# AblationChannel.net
KiCad netlist of a schematic drawn in Altium Designer
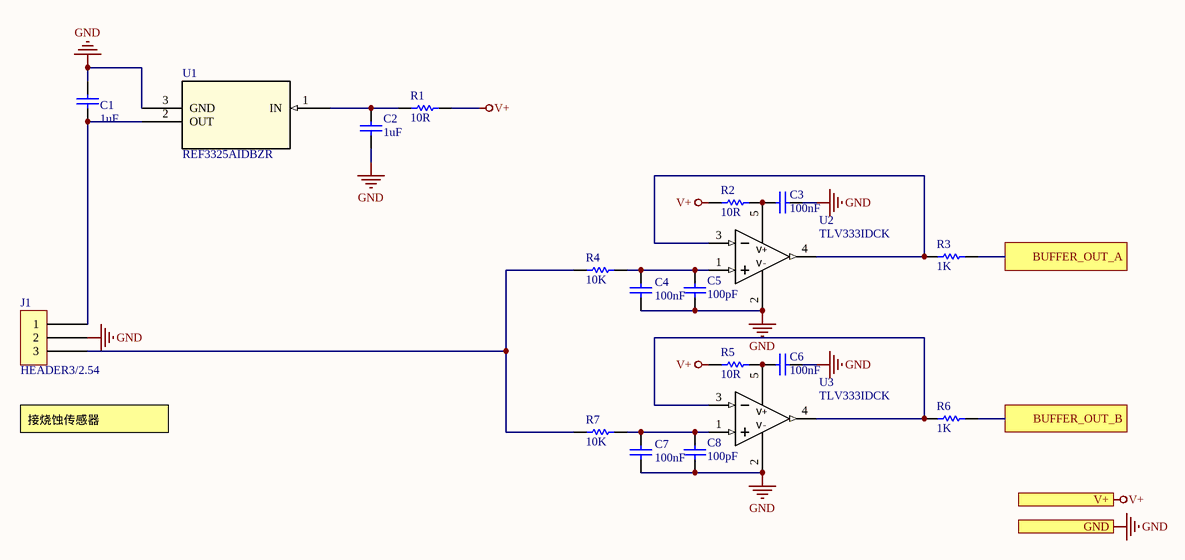
[diagram p0: AblationChannel.SchDoc]

(export (version "E")
  (design (tool "Eeschema 10.0.6"))
  (components
    (comp (ref "C1")
      (value "1uF")
      (footprint "R0603_C")
      (description "精度 ±10% \r\n容值 1uF \r\n额定电压 50V \r\n温漂系数（介质材料) X7R")
      (libsource (lib "00Lib") (part "1uF/0603/50V"))
    )
    (comp (ref "C2")
      (value "1uF")
      (footprint "R0603_C")
      (description "精度 ±10% \r\n容值 1uF \r\n额定电压 50V \r\n温漂系数（介质材料) X7R")
      (libsource (lib "00Lib") (part "1uF/0603/50V"))
    )
    (comp (ref "C3")
      (value "100nF")
      (footprint "R0603_C")
      (description "精度 ±10% \r\n容值 100nF \r\n额定电压 50V \r\n温漂系数（介质材料) X7R")
      (libsource (lib "00Lib") (part "100nF/0603/50V"))
    )
    (comp (ref "C4")
      (value "100nF")
      (footprint "R0603_C")
      (description "精度 ±10% \r\n容值 100nF \r\n额定电压 50V \r\n温漂系数（介质材料) X7R")
      (libsource (lib "00Lib") (part "100nF/0603/50V"))
    )
    (comp (ref "C5")
      (value "100pF")
      (footprint "R0603_C")
      (description "精度 ±5% \r\n容值 100pF \r\n额定电压 50V \r\n温漂系数（介质材料) C0G")
      (libsource (lib "00Lib") (part "100pF/0603/50V"))
    )
    (comp (ref "C6")
      (value "100nF")
      (footprint "R0603_C")
      (description "精度 ±10% \r\n容值 100nF \r\n额定电压 50V \r\n温漂系数（介质材料) X7R")
      (libsource (lib "00Lib") (part "100nF/0603/50V"))
    )
    (comp (ref "C7")
      (value "100nF")
      (footprint "R0603_C")
      (description "精度 ±10% \r\n容值 100nF \r\n额定电压 50V \r\n温漂系数（介质材料) X7R")
      (libsource (lib "00Lib") (part "100nF/0603/50V"))
    )
    (comp (ref "C8")
      (value "100pF")
      (footprint "R0603_C")
      (description "精度 ±5% \r\n容值 100pF \r\n额定电压 50V \r\n温漂系数（介质材料) C0G")
      (libsource (lib "00Lib") (part "100pF/0603/50V"))
    )
    (comp (ref "J1")
      (value "HEADER3/2.54")
      (footprint "SIP3/2.54")
      (description "3pin,单排,2.54mm间距")
      (libsource (lib "00Lib") (part "HEADER3/2.54"))
    )
    (comp (ref "R1")
      (value "10R")
      (footprint "R0603_R")
      (description "精度 ±1% \r\n阻值 10Ω \r\n温度系数 ±100ppm/℃ \r\n功率 0.1W")
      (libsource (lib "00Lib") (part "10R/0603"))
    )
    (comp (ref "R2")
      (value "10R")
      (footprint "R0603_R")
      (description "精度 ±1% \r\n阻值 10Ω \r\n温度系数 ±100ppm/℃ \r\n功率 0.1W")
      (libsource (lib "00Lib") (part "10R/0603"))
    )
    (comp (ref "R3")
      (value "1K")
      (footprint "R0603_R")
      (description "精度 ±1% \r\n温度系数 ±100ppm/℃ \r\n阻值 1kΩ \r\n功率 0.1W")
      (libsource (lib "00Lib") (part "1K/0603"))
    )
    (comp (ref "R4")
      (value "10K")
      (footprint "R0603_R")
      (description "精度 ±1% \r\n温度系数 ±100ppm/℃ \r\n阻值 10kΩ \r\n功率 0.1W")
      (libsource (lib "00Lib") (part "10K/0603"))
    )
    (comp (ref "R5")
      (value "10R")
      (footprint "R0603_R")
      (description "精度 ±1% \r\n阻值 10Ω \r\n温度系数 ±100ppm/℃ \r\n功率 0.1W")
      (libsource (lib "00Lib") (part "10R/0603"))
    )
    (comp (ref "R6")
      (value "1K")
      (footprint "R0603_R")
      (description "精度 ±1% \r\n温度系数 ±100ppm/℃ \r\n阻值 1kΩ \r\n功率 0.1W")
      (libsource (lib "00Lib") (part "1K/0603"))
    )
    (comp (ref "R7")
      (value "10K")
      (footprint "R0603_R")
      (description "精度 ±1% \r\n温度系数 ±100ppm/℃ \r\n阻值 10kΩ \r\n功率 0.1W")
      (libsource (lib "00Lib") (part "10K/0603"))
    )
    (comp (ref "U1")
      (value "REF3325AIDBZR")
      (footprint "SOT-23(SOT-23-3)")
      (libsource (lib "00Lib") (part "REF3325AIDBZR"))
    )
    (comp (ref "U2")
      (value "TLV333IDCK")
      (footprint "DCK0005A_N")
      (description "电源电压 1.8V ~ 5.5V, ±0.9V ~ 2.75V\r\n增益带宽积（GBP） 350kHz \r\n压摆率（SR） 0.16 V/us \r\n工作温度 -40°C ~ 125°C")
      (libsource (lib "00Lib") (part "TLV333IDCK"))
    )
    (comp (ref "U3")
      (value "TLV333IDCK")
      (footprint "DCK0005A_N")
      (description "电源电压 1.8V ~ 5.5V, ±0.9V ~ 2.75V\r\n增益带宽积（GBP） 350kHz \r\n压摆率（SR） 0.16 V/us \r\n工作温度 -40°C ~ 125°C")
      (libsource (lib "00Lib") (part "TLV333IDCK"))
    )
  )
  (nets
    (net (code "1") (name "/BUFFER_OUT_A") (class "Default")
      (node (ref "R3") (pin "2") (pinfunction "2_2") (pintype "passive"))
    )
    (net (code "2") (name "/BUFFER_OUT_B") (class "Default")
      (node (ref "R6") (pin "2") (pinfunction "2_2") (pintype "passive"))
    )
    (net (code "3") (name "GND") (class "Default")
      (node (ref "C1") (pin "1") (pinfunction "1_1") (pintype "passive"))
      (node (ref "C2") (pin "1") (pinfunction "1_1") (pintype "passive"))
      (node (ref "C3") (pin "1") (pinfunction "1_1") (pintype "passive"))
      (node (ref "C4") (pin "2") (pinfunction "2_2") (pintype "passive"))
      (node (ref "C5") (pin "1") (pinfunction "1_1") (pintype "passive"))
      (node (ref "C6") (pin "1") (pinfunction "1_1") (pintype "passive"))
      (node (ref "C7") (pin "2") (pinfunction "2_2") (pintype "passive"))
      (node (ref "C8") (pin "1") (pinfunction "1_1") (pintype "passive"))
      (node (ref "J1") (pin "2") (pinfunction "2_2") (pintype "passive"))
      (node (ref "U1") (pin "3") (pinfunction "GND_3") (pintype "power_in"))
      (node (ref "U2") (pin "2") (pinfunction "V-_2") (pintype "power_in"))
      (node (ref "U3") (pin "2") (pinfunction "V-_2") (pintype "power_in"))
    )
    (net (code "4") (name "Net-(J1-Pad3)") (class "Default")
      (node (ref "J1") (pin "3") (pinfunction "3_3") (pintype "passive"))
      (node (ref "R4") (pin "1") (pinfunction "1_1") (pintype "passive"))
      (node (ref "R7") (pin "1") (pinfunction "1_1") (pintype "passive"))
    )
    (net (code "5") (name "Net-(U1-IN)") (class "Default")
      (node (ref "C2") (pin "2") (pinfunction "2_2") (pintype "passive"))
      (node (ref "R1") (pin "2") (pinfunction "2_2") (pintype "passive"))
      (node (ref "U1") (pin "1") (pinfunction "IN_1") (pintype "input"))
    )
    (net (code "6") (name "Net-(U1-OUT)") (class "Default")
      (node (ref "C1") (pin "2") (pinfunction "2_2") (pintype "passive"))
      (node (ref "J1") (pin "1") (pinfunction "1_1") (pintype "passive"))
      (node (ref "U1") (pin "2") (pinfunction "OUT_2") (pintype "power_in"))
    )
    (net (code "7") (name "Net-(U2-IN+)") (class "Default")
      (node (ref "C4") (pin "1") (pinfunction "1_1") (pintype "passive"))
      (node (ref "C5") (pin "2") (pinfunction "2_2") (pintype "passive"))
      (node (ref "R4") (pin "2") (pinfunction "2_2") (pintype "passive"))
      (node (ref "U2") (pin "1") (pinfunction "IN+_1") (pintype "input"))
    )
    (net (code "8") (name "Net-(U2-IN-)") (class "Default")
      (node (ref "R3") (pin "1") (pinfunction "1_1") (pintype "passive"))
      (node (ref "U2") (pin "3") (pinfunction "IN-_3") (pintype "input"))
      (node (ref "U2") (pin "4") (pinfunction "OUT_4") (pintype "output"))
    )
    (net (code "9") (name "Net-(U2-V+)") (class "Default")
      (node (ref "C3") (pin "2") (pinfunction "2_2") (pintype "passive"))
      (node (ref "R2") (pin "1") (pinfunction "1_1") (pintype "passive"))
      (node (ref "U2") (pin "5") (pinfunction "V+_5") (pintype "power_in"))
    )
    (net (code "10") (name "Net-(U3-IN+)") (class "Default")
      (node (ref "C7") (pin "1") (pinfunction "1_1") (pintype "passive"))
      (node (ref "C8") (pin "2") (pinfunction "2_2") (pintype "passive"))
      (node (ref "R7") (pin "2") (pinfunction "2_2") (pintype "passive"))
      (node (ref "U3") (pin "1") (pinfunction "IN+_1") (pintype "input"))
    )
    (net (code "11") (name "Net-(U3-IN-)") (class "Default")
      (node (ref "R6") (pin "1") (pinfunction "1_1") (pintype "passive"))
      (node (ref "U3") (pin "3") (pinfunction "IN-_3") (pintype "input"))
      (node (ref "U3") (pin "4") (pinfunction "OUT_4") (pintype "output"))
    )
    (net (code "12") (name "Net-(U3-V+)") (class "Default")
      (node (ref "C6") (pin "2") (pinfunction "2_2") (pintype "passive"))
      (node (ref "R5") (pin "1") (pinfunction "1_1") (pintype "passive"))
      (node (ref "U3") (pin "5") (pinfunction "V+_5") (pintype "power_in"))
    )
    (net (code "13") (name "V+") (class "Default")
      (node (ref "R1") (pin "1") (pinfunction "1_1") (pintype "passive"))
      (node (ref "R2") (pin "2") (pinfunction "2_2") (pintype "passive"))
      (node (ref "R5") (pin "2") (pinfunction "2_2") (pintype "passive"))
    )
  )
)
